# NEW.net
KiCad netlist of a schematic drawn in EAGLE
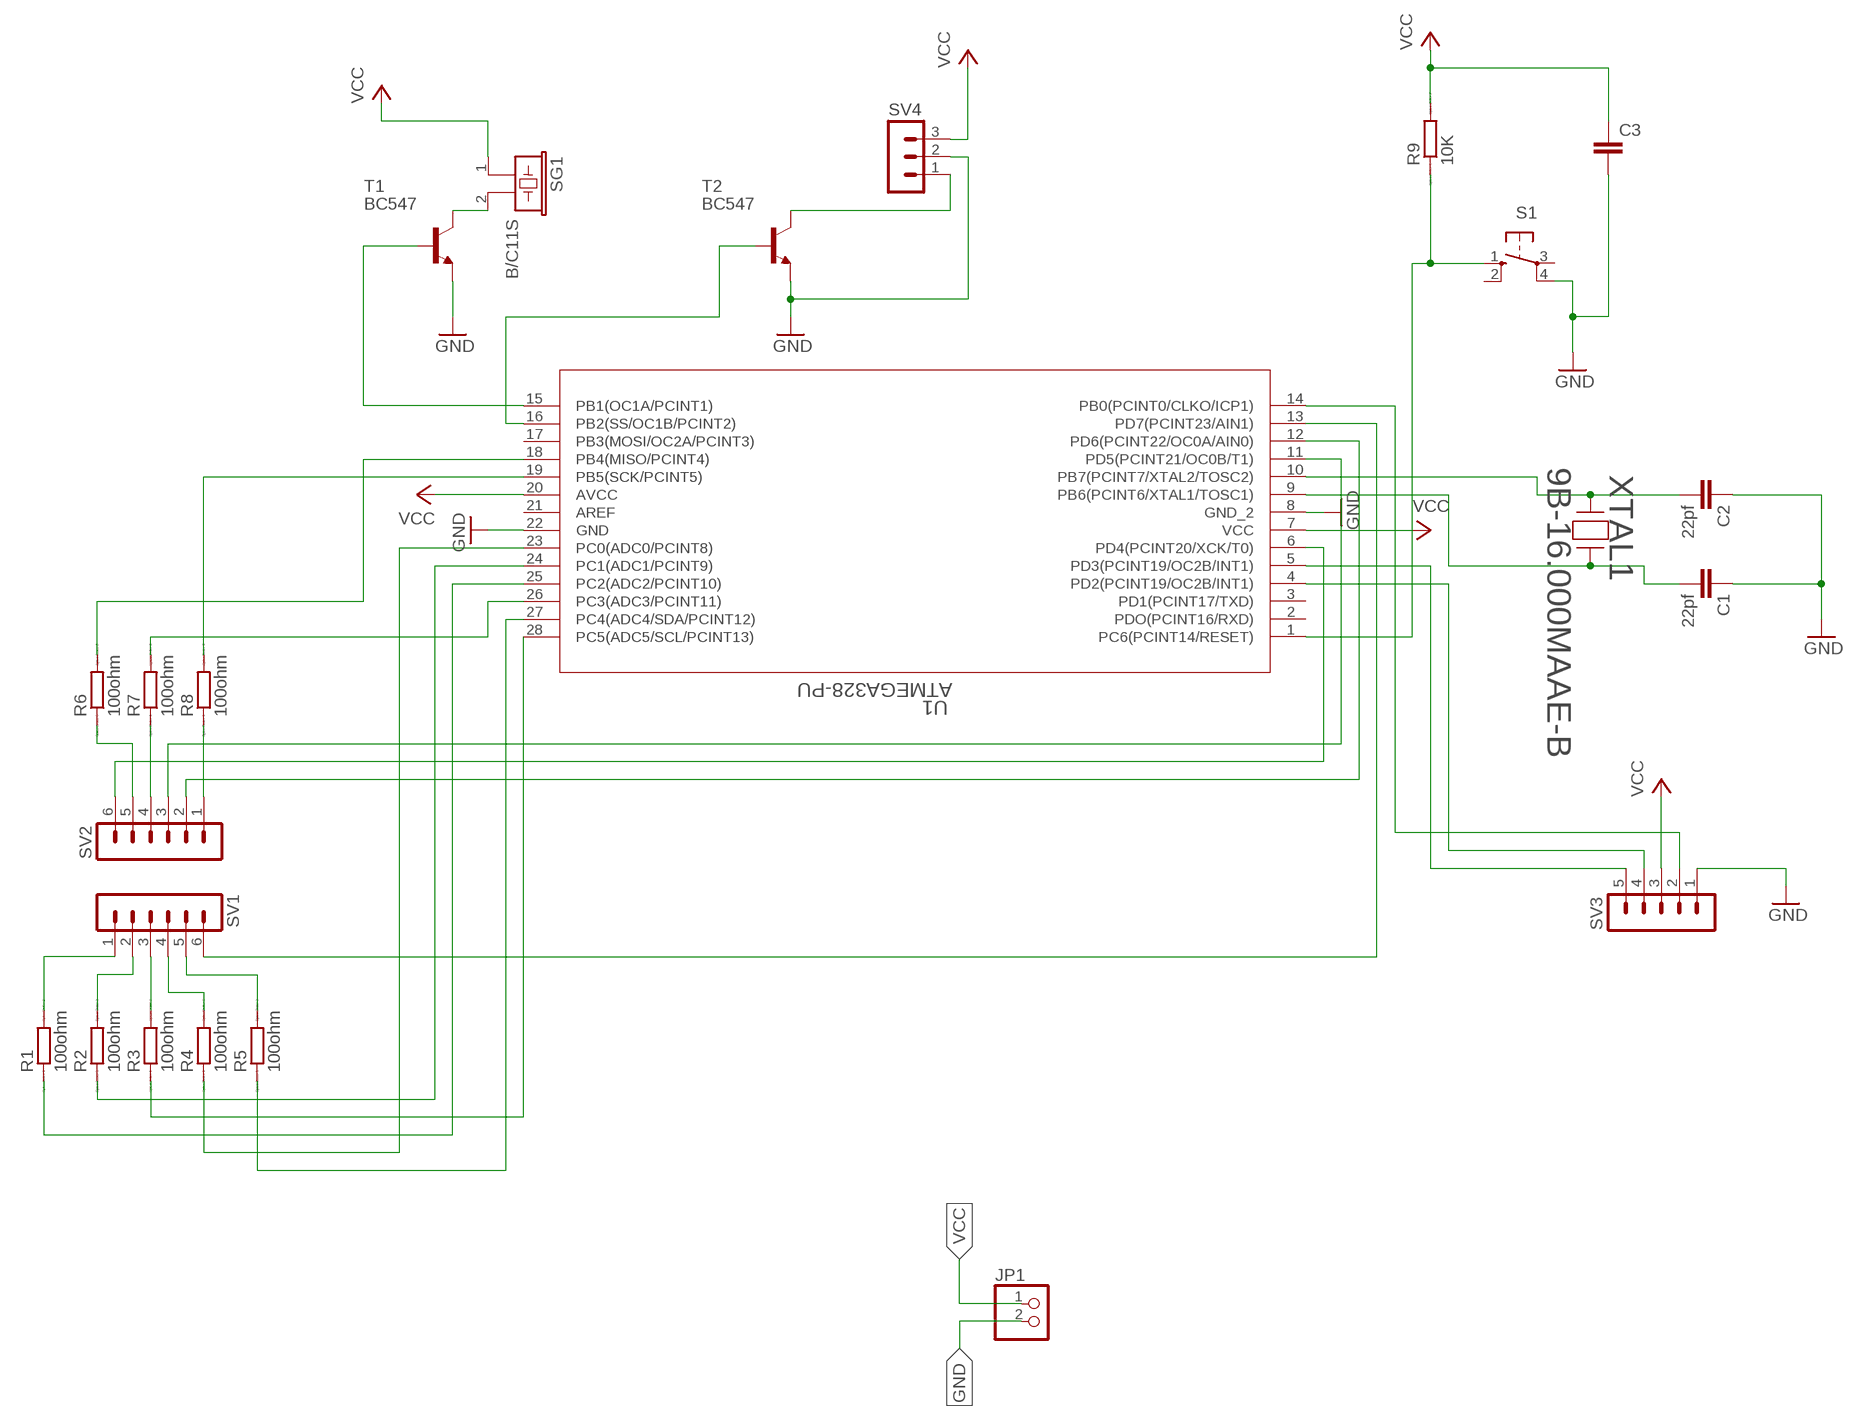
[diagram p0: schematic, sheet 1]

(export (version "E")
  (design (tool "Eeschema 10.0.6"))
  (components
    (comp (ref "C1")
      (value "22pf")
      (footprint "eagle-import:C2.5-3")
      (libsource (lib "eagle-import") (part "C2,5-3"))
    )
    (comp (ref "C2")
      (value "22pf")
      (footprint "eagle-import:C2.5-3")
      (libsource (lib "eagle-import") (part "C2,5-3"))
    )
    (comp (ref "C3")
      (value "C5/3")
      (footprint "eagle-import:C5B3")
      (libsource (lib "eagle-import") (part "C5/3"))
    )
    (comp (ref "JP1")
      (value "PINHD-1X2")
      (footprint "eagle-import:1X02")
      (libsource (lib "eagle-import") (part "PINHD-1X2"))
    )
    (comp (ref "R1")
      (value "100ohm")
      (footprint "eagle-import:0204_7")
      (libsource (lib "eagle-import") (part "R0204/7"))
    )
    (comp (ref "R2")
      (value "100ohm")
      (footprint "eagle-import:0204_7")
      (libsource (lib "eagle-import") (part "R0204/7"))
    )
    (comp (ref "R3")
      (value "100ohm")
      (footprint "eagle-import:0204_7")
      (libsource (lib "eagle-import") (part "R0204/7"))
    )
    (comp (ref "R4")
      (value "100ohm")
      (footprint "eagle-import:0204_7")
      (libsource (lib "eagle-import") (part "R0204/7"))
    )
    (comp (ref "R5")
      (value "100ohm")
      (footprint "eagle-import:0204_7")
      (libsource (lib "eagle-import") (part "R0204/7"))
    )
    (comp (ref "R6")
      (value "100ohm")
      (footprint "eagle-import:0204_7")
      (libsource (lib "eagle-import") (part "R0204/7"))
    )
    (comp (ref "R7")
      (value "100ohm")
      (footprint "eagle-import:0204_7")
      (libsource (lib "eagle-import") (part "R0204/7"))
    )
    (comp (ref "R8")
      (value "100ohm")
      (footprint "eagle-import:0204_7")
      (libsource (lib "eagle-import") (part "R0204/7"))
    )
    (comp (ref "R9")
      (value "10K")
      (footprint "eagle-import:0204_7")
      (libsource (lib "eagle-import") (part "R0204/7"))
    )
    (comp (ref "S1")
      (value "10-XX")
      (footprint "eagle-import:B3F-10XX")
      (fields (field (name "MPN") "B3F-1000"))
      (libsource (lib "eagle-import") (part "10-XX"))
    )
    (comp (ref "SG1")
      (value "B/C11S")
      (footprint "eagle-import:B_C11S")
      (libsource (lib "eagle-import") (part "B/C11S"))
    )
    (comp (ref "SV1")
      (value "MA06-1")
      (footprint "eagle-import:MA06-1")
      (libsource (lib "eagle-import") (part "MA06-1"))
    )
    (comp (ref "SV2")
      (value "MA06-1")
      (footprint "eagle-import:MA06-1")
      (libsource (lib "eagle-import") (part "MA06-1"))
    )
    (comp (ref "SV3")
      (value "MA05-1")
      (footprint "eagle-import:MA05-1")
      (libsource (lib "eagle-import") (part "MA05-1"))
    )
    (comp (ref "SV4")
      (value "MA03-1")
      (footprint "eagle-import:MA03-1")
      (libsource (lib "eagle-import") (part "MA03-1"))
    )
    (comp (ref "T1")
      (value "BC547")
      (footprint "eagle-import:TO92")
      (libsource (lib "eagle-import") (part "BC547"))
    )
    (comp (ref "T2")
      (value "BC547")
      (footprint "eagle-import:TO92")
      (libsource (lib "eagle-import") (part "BC547"))
    )
    (comp (ref "U1")
      (value "ATMEGA328-PU")
      (footprint "eagle-import:28P3_SPDIP28_SP_MCH")
      (fields (field (name "COPYRIGHT") "Copyright (C) 2023 Ultra Librarian. All rights reserved."))
      (libsource (lib "eagle-import") (part "ATMEGA328-PU"))
    )
    (comp (ref "XTAL1")
      (value "9B-16.000MAAE-B")
      (footprint "eagle-import:9B-16.000MAAE-B_TXC")
      (fields (field (name "COPYRIGHT") "Copyright (C) 2023 Ultra Librarian. All rights reserved."))
      (libsource (lib "eagle-import") (part "9B-16.000MAAE-B"))
    )
  )
  (nets
    (net (code "1") (name "GND") (class "Default")
      (node (ref "C1") (pin "1") (pinfunction "1_1") (pintype "passive"))
      (node (ref "C2") (pin "1") (pinfunction "1_1") (pintype "passive"))
      (node (ref "C3") (pin "2") (pinfunction "2_2") (pintype "passive"))
      (node (ref "JP1") (pin "2") (pinfunction "2_2") (pintype "passive"))
      (node (ref "S1") (pin "4") (pinfunction "P1_4") (pintype "passive"))
      (node (ref "SV3") (pin "1") (pinfunction "1_1") (pintype "passive"))
      (node (ref "SV4") (pin "2") (pinfunction "2_2") (pintype "passive"))
      (node (ref "T1") (pin "1") (pinfunction "E_1") (pintype "passive"))
      (node (ref "T2") (pin "1") (pinfunction "E_1") (pintype "passive"))
      (node (ref "U1") (pin "22") (pinfunction "GND_22") (pintype "passive"))
      (node (ref "U1") (pin "8") (pinfunction "GND_2_8") (pintype "passive"))
    )
    (net (code "2") (name "Net-(R1-Pad2)") (class "Default")
      (node (ref "R1") (pin "2") (pinfunction "2_2") (pintype "passive"))
      (node (ref "SV1") (pin "1") (pinfunction "1_1") (pintype "passive"))
    )
    (net (code "3") (name "Net-(R2-Pad2)") (class "Default")
      (node (ref "R2") (pin "2") (pinfunction "2_2") (pintype "passive"))
      (node (ref "SV1") (pin "2") (pinfunction "2_2") (pintype "passive"))
    )
    (net (code "4") (name "Net-(R3-Pad2)") (class "Default")
      (node (ref "R3") (pin "2") (pinfunction "2_2") (pintype "passive"))
      (node (ref "SV1") (pin "3") (pinfunction "3_3") (pintype "passive"))
    )
    (net (code "5") (name "Net-(R4-Pad2)") (class "Default")
      (node (ref "R4") (pin "2") (pinfunction "2_2") (pintype "passive"))
      (node (ref "SV1") (pin "4") (pinfunction "4_4") (pintype "passive"))
    )
    (net (code "6") (name "Net-(R5-Pad2)") (class "Default")
      (node (ref "R5") (pin "2") (pinfunction "2_2") (pintype "passive"))
      (node (ref "SV1") (pin "5") (pinfunction "5_5") (pintype "passive"))
    )
    (net (code "7") (name "Net-(R6-Pad1)") (class "Default")
      (node (ref "R6") (pin "1") (pinfunction "1_1") (pintype "passive"))
      (node (ref "SV2") (pin "5") (pinfunction "5_5") (pintype "passive"))
    )
    (net (code "8") (name "Net-(R7-Pad1)") (class "Default")
      (node (ref "R7") (pin "1") (pinfunction "1_1") (pintype "passive"))
      (node (ref "SV2") (pin "4") (pinfunction "4_4") (pintype "passive"))
    )
    (net (code "9") (name "Net-(R8-Pad1)") (class "Default")
      (node (ref "R8") (pin "1") (pinfunction "1_1") (pintype "passive"))
      (node (ref "SV2") (pin "1") (pinfunction "1_1") (pintype "passive"))
    )
    (net (code "10") (name "Net-(S1-S)") (class "Default")
      (node (ref "R9") (pin "1") (pinfunction "1_1") (pintype "passive"))
      (node (ref "S1") (pin "1") (pinfunction "S_1") (pintype "passive"))
      (node (ref "U1") (pin "1") (pinfunction "PC6(PCINT14/RESET)_1") (pintype "bidirectional"))
    )
    (net (code "11") (name "Net-(T1-B)") (class "Default")
      (node (ref "T1") (pin "2") (pinfunction "B_2") (pintype "passive"))
      (node (ref "U1") (pin "15") (pinfunction "PB1(OC1A/PCINT1)_15") (pintype "bidirectional"))
    )
    (net (code "12") (name "Net-(T1-C)") (class "Default")
      (node (ref "SG1") (pin "2") (pinfunction "2_2") (pintype "passive"))
      (node (ref "T1") (pin "3") (pinfunction "C_3") (pintype "passive"))
    )
    (net (code "13") (name "Net-(T2-B)") (class "Default")
      (node (ref "T2") (pin "2") (pinfunction "B_2") (pintype "passive"))
      (node (ref "U1") (pin "16") (pinfunction "PB2(SS/OC1B/PCINT2)_16") (pintype "bidirectional"))
    )
    (net (code "14") (name "Net-(T2-C)") (class "Default")
      (node (ref "SV4") (pin "1") (pinfunction "1_1") (pintype "passive"))
      (node (ref "T2") (pin "3") (pinfunction "C_3") (pintype "passive"))
    )
    (net (code "15") (name "Net-(U1-PB0(PCINT0{slash}CLKO{slash}ICP1))") (class "Default")
      (node (ref "SV3") (pin "2") (pinfunction "2_2") (pintype "passive"))
      (node (ref "SV3") (pin "5") (pinfunction "5_5") (pintype "passive"))
      (node (ref "U1") (pin "14") (pinfunction "PB0(PCINT0/CLKO/ICP1)_14") (pintype "bidirectional"))
      (node (ref "U1") (pin "5") (pinfunction "PD3(PCINT19/OC2B/INT1)_5") (pintype "bidirectional"))
    )
    (net (code "16") (name "Net-(U1-PB4(MISO{slash}PCINT4))") (class "Default")
      (node (ref "R6") (pin "2") (pinfunction "2_2") (pintype "passive"))
      (node (ref "U1") (pin "18") (pinfunction "PB4(MISO/PCINT4)_18") (pintype "bidirectional"))
    )
    (net (code "17") (name "Net-(U1-PB5(SCK{slash}PCINT5))") (class "Default")
      (node (ref "R8") (pin "2") (pinfunction "2_2") (pintype "passive"))
      (node (ref "U1") (pin "19") (pinfunction "PB5(SCK/PCINT5)_19") (pintype "bidirectional"))
    )
    (net (code "18") (name "Net-(U1-PB6(PCINT6{slash}XTAL1{slash}TOSC1))") (class "Default")
      (node (ref "C1") (pin "2") (pinfunction "2_2") (pintype "passive"))
      (node (ref "U1") (pin "9") (pinfunction "PB6(PCINT6/XTAL1/TOSC1)_9") (pintype "bidirectional"))
      (node (ref "XTAL1") (pin "2") (pinfunction "2_2") (pintype "passive"))
    )
    (net (code "19") (name "Net-(U1-PB7(PCINT7{slash}XTAL2{slash}TOSC2))") (class "Default")
      (node (ref "C2") (pin "2") (pinfunction "2_2") (pintype "passive"))
      (node (ref "U1") (pin "10") (pinfunction "PB7(PCINT7/XTAL2/TOSC2)_10") (pintype "bidirectional"))
      (node (ref "XTAL1") (pin "1") (pinfunction "1_1") (pintype "passive"))
    )
    (net (code "20") (name "Net-(U1-PC0(ADC0{slash}PCINT8))") (class "Default")
      (node (ref "R4") (pin "1") (pinfunction "1_1") (pintype "passive"))
      (node (ref "U1") (pin "23") (pinfunction "PC0(ADC0/PCINT8)_23") (pintype "bidirectional"))
    )
    (net (code "21") (name "Net-(U1-PC1(ADC1{slash}PCINT9))") (class "Default")
      (node (ref "R2") (pin "1") (pinfunction "1_1") (pintype "passive"))
      (node (ref "U1") (pin "24") (pinfunction "PC1(ADC1/PCINT9)_24") (pintype "bidirectional"))
    )
    (net (code "22") (name "Net-(U1-PC2(ADC2{slash}PCINT10))") (class "Default")
      (node (ref "R1") (pin "1") (pinfunction "1_1") (pintype "passive"))
      (node (ref "U1") (pin "25") (pinfunction "PC2(ADC2/PCINT10)_25") (pintype "bidirectional"))
    )
    (net (code "23") (name "Net-(U1-PC3(ADC3{slash}PCINT11))") (class "Default")
      (node (ref "R7") (pin "2") (pinfunction "2_2") (pintype "passive"))
      (node (ref "U1") (pin "26") (pinfunction "PC3(ADC3/PCINT11)_26") (pintype "bidirectional"))
    )
    (net (code "24") (name "Net-(U1-PC4(ADC4{slash}SDA{slash}PCINT12))") (class "Default")
      (node (ref "R5") (pin "1") (pinfunction "1_1") (pintype "passive"))
      (node (ref "U1") (pin "27") (pinfunction "PC4(ADC4/SDA/PCINT12)_27") (pintype "bidirectional"))
    )
    (net (code "25") (name "Net-(U1-PC5(ADC5{slash}SCL{slash}PCINT13))") (class "Default")
      (node (ref "R3") (pin "1") (pinfunction "1_1") (pintype "passive"))
      (node (ref "U1") (pin "28") (pinfunction "PC5(ADC5/SCL/PCINT13)_28") (pintype "bidirectional"))
    )
    (net (code "26") (name "Net-(U1-PD2(PCINT19{slash}OC2B{slash}INT1))") (class "Default")
      (node (ref "SV3") (pin "4") (pinfunction "4_4") (pintype "passive"))
      (node (ref "U1") (pin "4") (pinfunction "PD2(PCINT19/OC2B/INT1)_4") (pintype "bidirectional"))
    )
    (net (code "27") (name "Net-(U1-PD4(PCINT20{slash}XCK{slash}T0))") (class "Default")
      (node (ref "SV2") (pin "6") (pinfunction "6_6") (pintype "passive"))
      (node (ref "U1") (pin "6") (pinfunction "PD4(PCINT20/XCK/T0)_6") (pintype "bidirectional"))
    )
    (net (code "28") (name "Net-(U1-PD5(PCINT21{slash}OC0B{slash}T1))") (class "Default")
      (node (ref "SV2") (pin "3") (pinfunction "3_3") (pintype "passive"))
      (node (ref "U1") (pin "11") (pinfunction "PD5(PCINT21/OC0B/T1)_11") (pintype "bidirectional"))
    )
    (net (code "29") (name "Net-(U1-PD6(PCINT22{slash}OC0A{slash}AIN0))") (class "Default")
      (node (ref "SV2") (pin "2") (pinfunction "2_2") (pintype "passive"))
      (node (ref "U1") (pin "12") (pinfunction "PD6(PCINT22/OC0A/AIN0)_12") (pintype "bidirectional"))
    )
    (net (code "30") (name "Net-(U1-PD7(PCINT23{slash}AIN1))") (class "Default")
      (node (ref "SV1") (pin "6") (pinfunction "6_6") (pintype "passive"))
      (node (ref "U1") (pin "13") (pinfunction "PD7(PCINT23/AIN1)_13") (pintype "bidirectional"))
    )
    (net (code "31") (name "VCC") (class "Default")
      (node (ref "C3") (pin "1") (pinfunction "1_1") (pintype "passive"))
      (node (ref "JP1") (pin "1") (pinfunction "1_1") (pintype "passive"))
      (node (ref "R9") (pin "2") (pinfunction "2_2") (pintype "passive"))
      (node (ref "SG1") (pin "1") (pinfunction "1_1") (pintype "passive"))
      (node (ref "SV3") (pin "3") (pinfunction "3_3") (pintype "passive"))
      (node (ref "SV4") (pin "3") (pinfunction "3_3") (pintype "passive"))
      (node (ref "U1") (pin "20") (pinfunction "AVCC_20") (pintype "power_in"))
      (node (ref "U1") (pin "7") (pinfunction "VCC_7") (pintype "power_in"))
    )
    (net (code "32") (name "unconnected-(S1-P-Pad3)") (class "Default")
      (node (ref "S1") (pin "3") (pinfunction "P_3") (pintype "passive"))
    )
    (net (code "33") (name "unconnected-(S1-S1-Pad2)") (class "Default")
      (node (ref "S1") (pin "2") (pinfunction "S1_2") (pintype "passive"))
    )
    (net (code "34") (name "unconnected-(U1-AREF-Pad21)") (class "Default")
      (node (ref "U1") (pin "21") (pinfunction "AREF_21") (pintype "passive"))
    )
    (net (code "35") (name "unconnected-(U1-PB3(MOSI{slash}OC2A{slash}PCINT3)-Pad17)") (class "Default")
      (node (ref "U1") (pin "17") (pinfunction "PB3(MOSI/OC2A/PCINT3)_17") (pintype "bidirectional"))
    )
    (net (code "36") (name "unconnected-(U1-PD1(PCINT17{slash}TXD)-Pad3)") (class "Default")
      (node (ref "U1") (pin "3") (pinfunction "PD1(PCINT17/TXD)_3") (pintype "bidirectional"))
    )
    (net (code "37") (name "unconnected-(U1-PDO(PCINT16{slash}RXD)-Pad2)") (class "Default")
      (node (ref "U1") (pin "2") (pinfunction "PDO(PCINT16/RXD)_2") (pintype "bidirectional"))
    )
  )
)
